# PiezoTL072Preamp.net
KiCad netlist of a schematic drawn in EAGLE
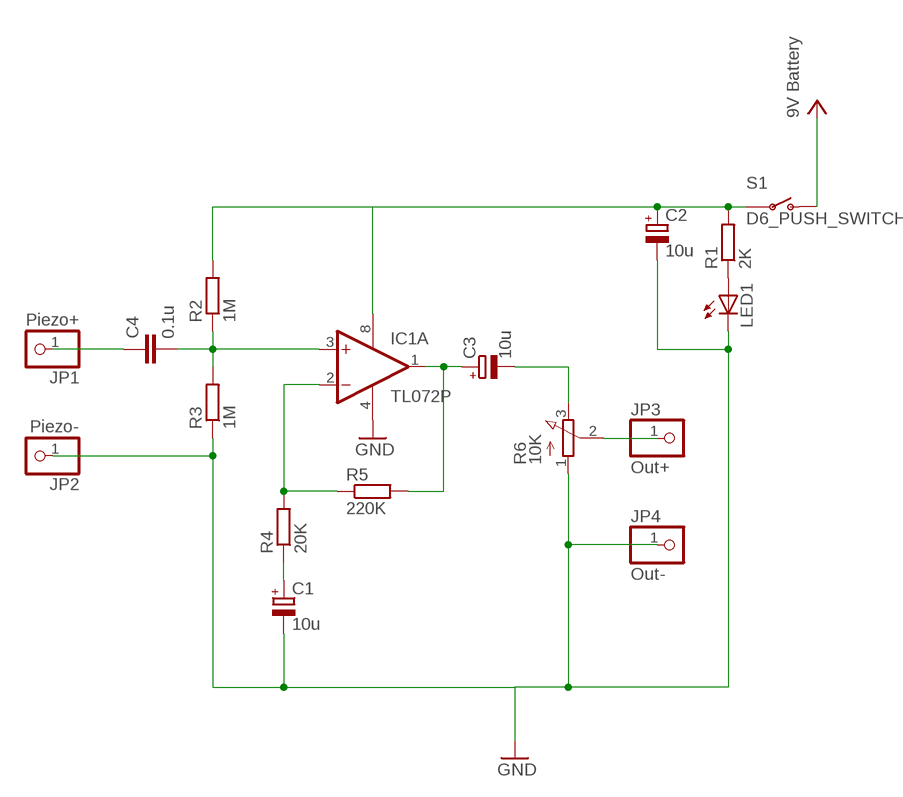
[diagram p0: schematic, sheet 1]

(export (version "E")
  (design (tool "Eeschema 10.0.6"))
  (components
    (comp (ref "C1")
      (value "10u")
      (footprint "eagle-import:B45181B")
      (libsource (lib "eagle-import") (part "CPOL-EUB45181B"))
    )
    (comp (ref "C2")
      (value "10u")
      (footprint "eagle-import:B45181B")
      (libsource (lib "eagle-import") (part "CPOL-EUB45181B"))
    )
    (comp (ref "C3")
      (value "10u")
      (footprint "eagle-import:B45181B")
      (libsource (lib "eagle-import") (part "CPOL-EUB45181B"))
    )
    (comp (ref "C4")
      (value "0.1u")
      (footprint "eagle-import:C025-030X050")
      (libsource (lib "eagle-import") (part "C-EU025-030X050"))
    )
    (comp (ref "IC1")
      (value "TL072P")
      (footprint "eagle-import:DIL08")
      (libsource (lib "eagle-import") (part "TL072P"))
    )
    (comp (ref "JP1")
      (value "Piezo+")
      (footprint "eagle-import:1X01")
      (libsource (lib "eagle-import") (part "PINHD-1X1"))
    )
    (comp (ref "JP2")
      (value "Piezo-")
      (footprint "eagle-import:1X01")
      (libsource (lib "eagle-import") (part "PINHD-1X1"))
    )
    (comp (ref "JP3")
      (value "Out+")
      (footprint "eagle-import:1X01")
      (libsource (lib "eagle-import") (part "PINHD-1X1"))
    )
    (comp (ref "JP4")
      (value "Out-")
      (footprint "eagle-import:1X01")
      (libsource (lib "eagle-import") (part "PINHD-1X1"))
    )
    (comp (ref "LED1")
      (value "LED5MM")
      (footprint "eagle-import:LED5MM")
      (libsource (lib "eagle-import") (part "LED5MM"))
    )
    (comp (ref "R1")
      (value "2K")
      (footprint "eagle-import:0204_7")
      (libsource (lib "eagle-import") (part "R-EU_0204/7"))
    )
    (comp (ref "R2")
      (value "1M")
      (footprint "eagle-import:0204_7")
      (libsource (lib "eagle-import") (part "R-EU_0204/7"))
    )
    (comp (ref "R3")
      (value "1M")
      (footprint "eagle-import:0204_7")
      (libsource (lib "eagle-import") (part "R-EU_0204/7"))
    )
    (comp (ref "R4")
      (value "20K")
      (footprint "eagle-import:0204_7")
      (libsource (lib "eagle-import") (part "R-EU_0204/7"))
    )
    (comp (ref "R5")
      (value "220K")
      (footprint "eagle-import:0204_7")
      (libsource (lib "eagle-import") (part "R-EU_0204/7"))
    )
    (comp (ref "R6")
      (value "10K")
      (footprint "eagle-import:EVUF")
      (libsource (lib "eagle-import") (part "EVUAF2"))
    )
    (comp (ref "S1")
      (value "D6_PUSH_SWITCH")
      (footprint "eagle-import:D6_PUSH_SWITCH")
      (libsource (lib "eagle-import") (part "D6_PUSH_SWITCH"))
    )
  )
  (nets
    (net (code "1") (name "9V Battery") (class "Default")
      (node (ref "S1") (pin "P$1") (pinfunction "O_P$1") (pintype "passive"))
      (node (ref "S1") (pin "P$2") (pinfunction "O_P$2") (pintype "passive"))
    )
    (net (code "2") (name "GND") (class "Default")
      (node (ref "C1") (pin "-") (pinfunction "-_-") (pintype "passive"))
      (node (ref "C2") (pin "-") (pinfunction "-_-") (pintype "passive"))
      (node (ref "IC1") (pin "4") (pinfunction "V-_4") (pintype "power_in"))
      (node (ref "JP2") (pin "1") (pinfunction "1_1") (pintype "passive"))
      (node (ref "JP4") (pin "1") (pinfunction "1_1") (pintype "passive"))
      (node (ref "LED1") (pin "K") (pinfunction "C_K") (pintype "passive"))
      (node (ref "R3") (pin "1") (pinfunction "1_1") (pintype "passive"))
      (node (ref "R6") (pin "1") (pinfunction "A_1") (pintype "passive"))
    )
    (net (code "3") (name "Net-(C1-Pad+)") (class "Default")
      (node (ref "C1") (pin "+") (pinfunction "+_+") (pintype "passive"))
      (node (ref "R4") (pin "1") (pinfunction "1_1") (pintype "passive"))
    )
    (net (code "4") (name "Net-(C4-Pad1)") (class "Default")
      (node (ref "C4") (pin "1") (pinfunction "1_1") (pintype "passive"))
      (node (ref "JP1") (pin "1") (pinfunction "1_1") (pintype "passive"))
    )
    (net (code "5") (name "Net-(IC1A-+IN)") (class "Default")
      (node (ref "C4") (pin "2") (pinfunction "2_2") (pintype "passive"))
      (node (ref "IC1") (pin "3") (pinfunction "+IN_3") (pintype "input"))
      (node (ref "R2") (pin "1") (pinfunction "1_1") (pintype "passive"))
      (node (ref "R3") (pin "2") (pinfunction "2_2") (pintype "passive"))
    )
    (net (code "6") (name "Net-(IC1A--IN)") (class "Default")
      (node (ref "IC1") (pin "2") (pinfunction "-IN_2") (pintype "input"))
      (node (ref "R4") (pin "2") (pinfunction "2_2") (pintype "passive"))
      (node (ref "R5") (pin "1") (pinfunction "1_1") (pintype "passive"))
    )
    (net (code "7") (name "Net-(IC1A-OUT)") (class "Default")
      (node (ref "C3") (pin "+") (pinfunction "+_+") (pintype "passive"))
      (node (ref "IC1") (pin "1") (pinfunction "OUT_1") (pintype "output"))
      (node (ref "R5") (pin "2") (pinfunction "2_2") (pintype "passive"))
    )
    (net (code "8") (name "Net-(IC1C-V+)") (class "Default")
      (node (ref "C2") (pin "+") (pinfunction "+_+") (pintype "passive"))
      (node (ref "IC1") (pin "8") (pinfunction "V+_8") (pintype "power_in"))
      (node (ref "R1") (pin "2") (pinfunction "2_2") (pintype "passive"))
      (node (ref "R2") (pin "2") (pinfunction "2_2") (pintype "passive"))
      (node (ref "S1") (pin "P$3") (pinfunction "P_P$3") (pintype "passive"))
      (node (ref "S1") (pin "P$4") (pinfunction "P_P$4") (pintype "passive"))
    )
    (net (code "9") (name "Net-(LED1-PadA)") (class "Default")
      (node (ref "LED1") (pin "A") (pinfunction "A_A") (pintype "passive"))
      (node (ref "R1") (pin "1") (pinfunction "1_1") (pintype "passive"))
    )
    (net (code "10") (name "Net-(R6-E)") (class "Default")
      (node (ref "C3") (pin "-") (pinfunction "-_-") (pintype "passive"))
      (node (ref "R6") (pin "3") (pinfunction "E_3") (pintype "passive"))
    )
    (net (code "11") (name "Net-(R6-S)") (class "Default")
      (node (ref "JP3") (pin "1") (pinfunction "1_1") (pintype "passive"))
      (node (ref "R6") (pin "2") (pinfunction "S_2") (pintype "passive"))
    )
  )
)
